# mcu.net
KiCad netlist of a schematic drawn in Altium Designer
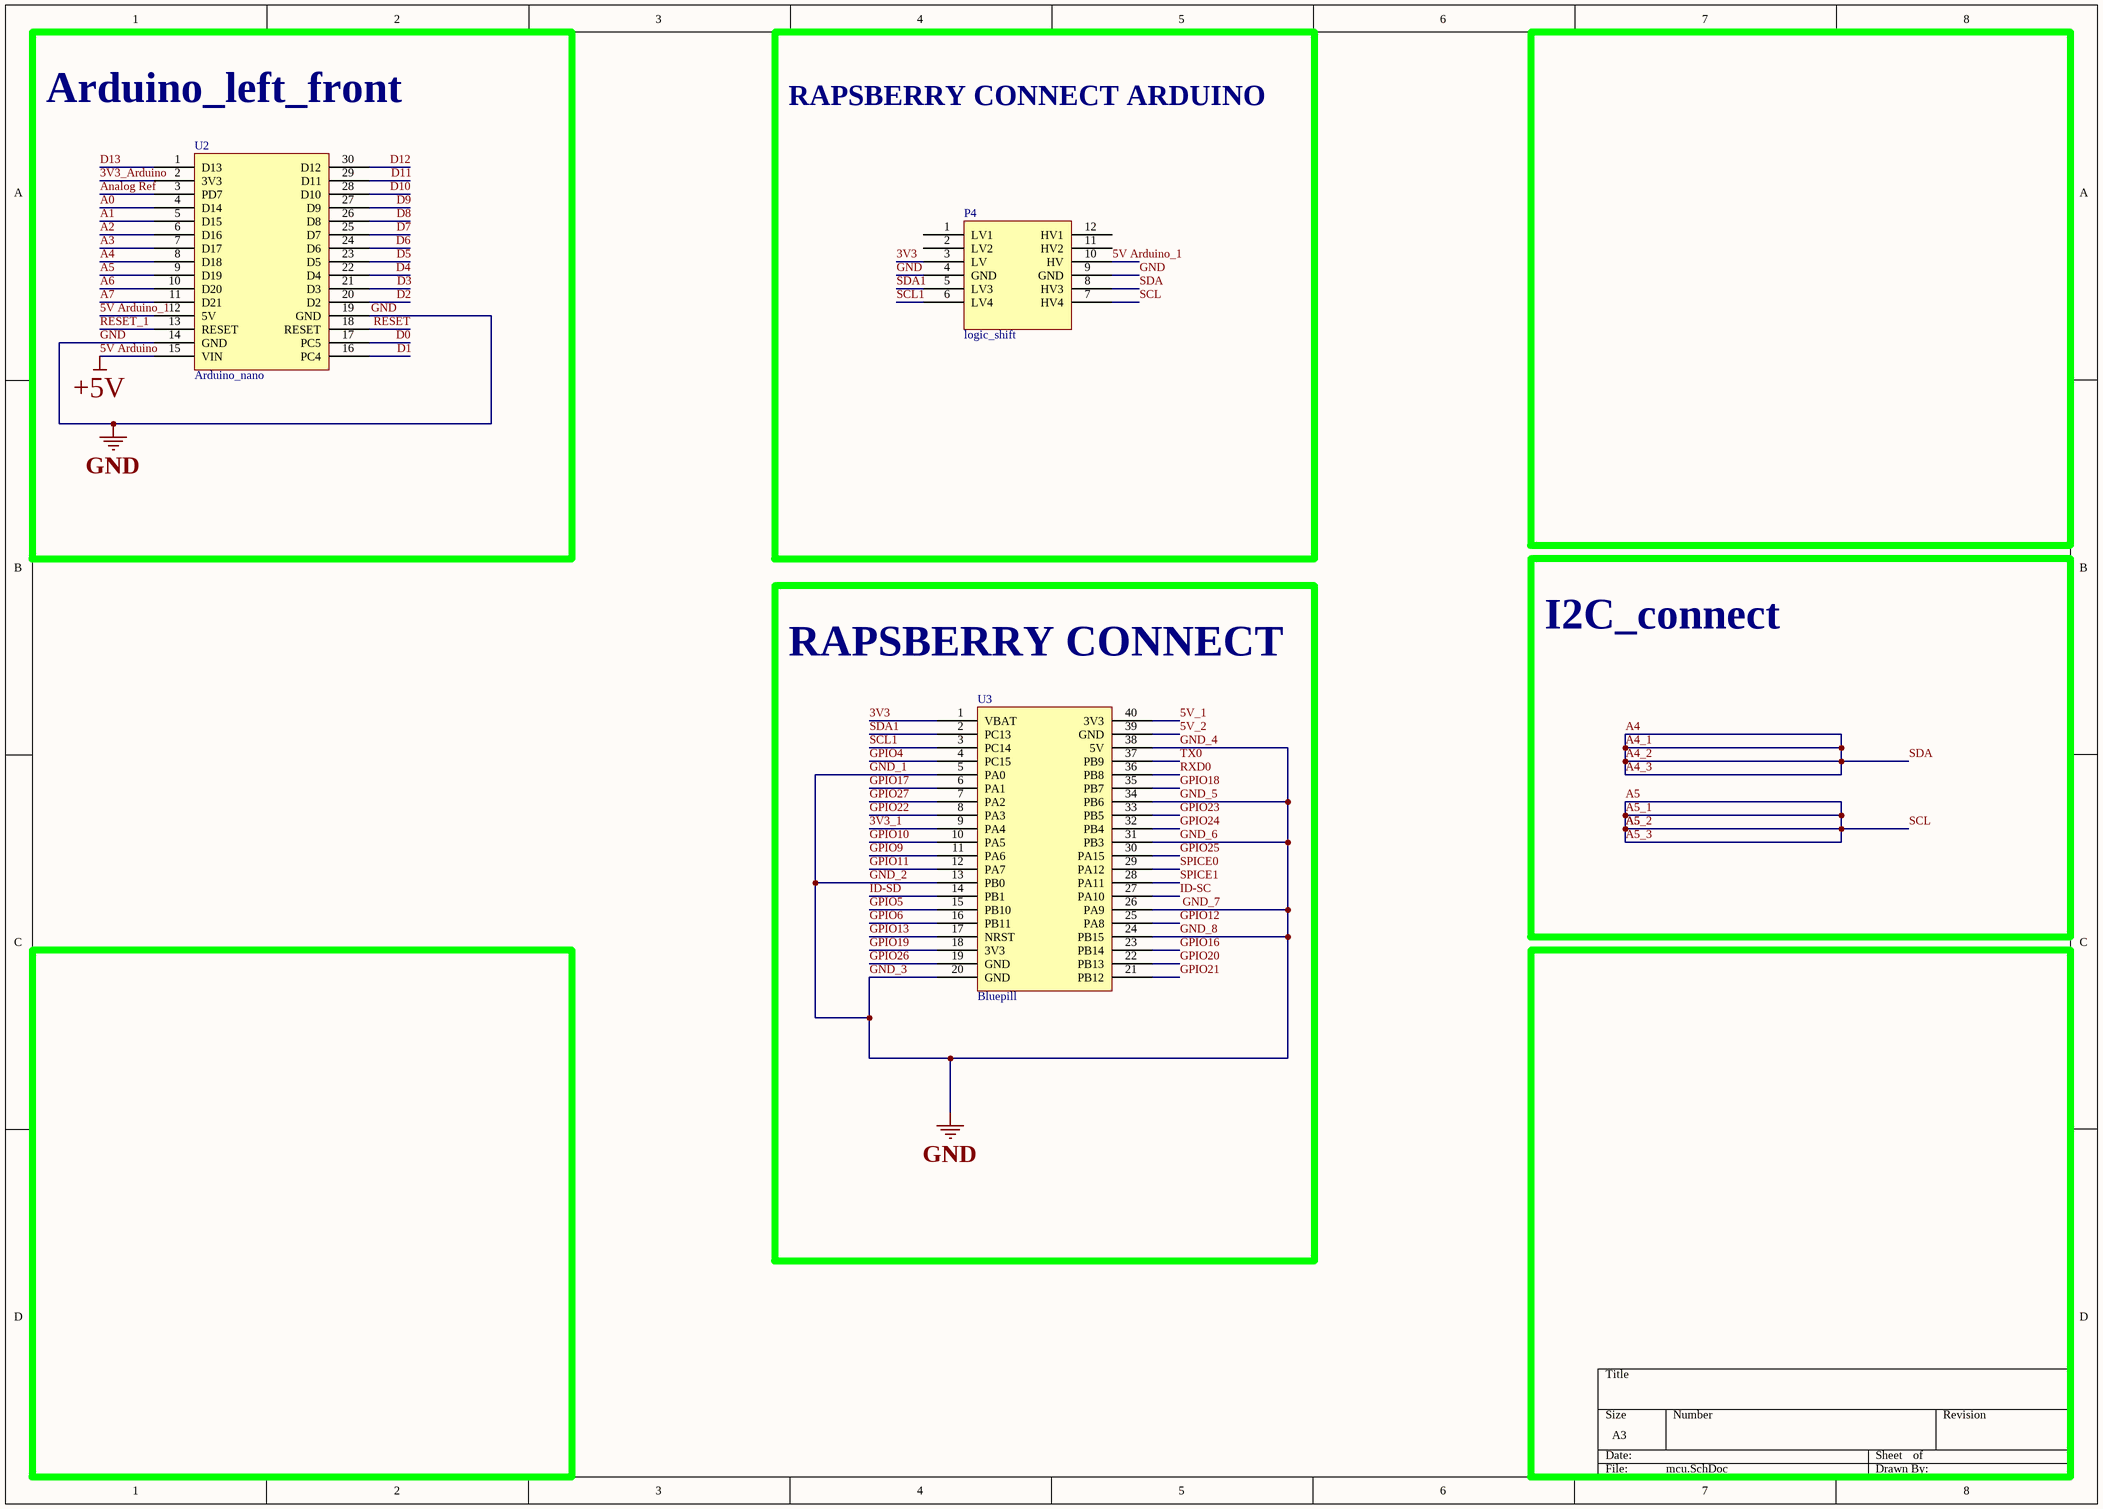
[diagram p0: mcu.SchDoc]

(export (version "E")
  (design (tool "Eeschema 10.0.6"))
  (components
    (comp (ref "P4")
      (value "logic_shift")
      (footprint "logic_convert")
      (libsource (lib "Integrated_Library1") (part "logic_shift"))
    )
    (comp (ref "U2")
      (value "Arduino_nano")
      (footprint "PCBComponent_1")
      (libsource (lib "Integrated_Library1") (part "Arduino_nano"))
    )
    (comp (ref "U3")
      (value "Bluepill")
      (footprint "STM32F103C8T6-Bluepill")
      (libsource (lib "Integrated_Library1") (part "STM32F103C8T6"))
    )
  )
  (nets
    (net (code "1") (name "+5V") (class "Default")
      (node (ref "U2") (pin "15") (pinfunction "VIN_15") (pintype "passive"))
    )
    (net (code "2") (name "/3V3") (class "Default")
      (node (ref "P4") (pin "3") (pinfunction "LV_3") (pintype "passive"))
      (node (ref "U3") (pin "1") (pinfunction "VBAT_1") (pintype "passive"))
    )
    (net (code "3") (name "/3V3_1") (class "Default")
      (node (ref "U3") (pin "9") (pinfunction "PA4_9") (pintype "passive"))
    )
    (net (code "4") (name "/3V3_Arduino") (class "Default")
      (node (ref "U2") (pin "2") (pinfunction "3V3_2") (pintype "passive"))
    )
    (net (code "5") (name "/5V Arduino_1") (class "Default")
      (node (ref "P4") (pin "10") (pinfunction "HV_10") (pintype "passive"))
      (node (ref "U2") (pin "12") (pinfunction "5V_12") (pintype "passive"))
    )
    (net (code "6") (name "/5V_1") (class "Default")
      (node (ref "U3") (pin "40") (pinfunction "3V3_40") (pintype "passive"))
    )
    (net (code "7") (name "/5V_2") (class "Default")
      (node (ref "U3") (pin "39") (pinfunction "GND_39") (pintype "passive"))
    )
    (net (code "8") (name "/A0") (class "Default")
      (node (ref "U2") (pin "4") (pinfunction "D14_4") (pintype "passive"))
    )
    (net (code "9") (name "/A1") (class "Default")
      (node (ref "U2") (pin "5") (pinfunction "D15_5") (pintype "passive"))
    )
    (net (code "10") (name "/A2") (class "Default")
      (node (ref "U2") (pin "6") (pinfunction "D16_6") (pintype "passive"))
    )
    (net (code "11") (name "/A3") (class "Default")
      (node (ref "U2") (pin "7") (pinfunction "D17_7") (pintype "passive"))
    )
    (net (code "12") (name "/A4") (class "Default")
      (node (ref "P4") (pin "8") (pinfunction "HV3_8") (pintype "passive"))
      (node (ref "U2") (pin "8") (pinfunction "D18_8") (pintype "passive"))
    )
    (net (code "13") (name "/A5") (class "Default")
      (node (ref "P4") (pin "7") (pinfunction "HV4_7") (pintype "passive"))
      (node (ref "U2") (pin "9") (pinfunction "D19_9") (pintype "passive"))
    )
    (net (code "14") (name "/A6") (class "Default")
      (node (ref "U2") (pin "10") (pinfunction "D20_10") (pintype "passive"))
    )
    (net (code "15") (name "/A7") (class "Default")
      (node (ref "U2") (pin "11") (pinfunction "D21_11") (pintype "passive"))
    )
    (net (code "16") (name "/Analog Ref") (class "Default")
      (node (ref "U2") (pin "3") (pinfunction "PD7_3") (pintype "passive"))
    )
    (net (code "17") (name "/D0") (class "Default")
      (node (ref "U2") (pin "17") (pinfunction "PC5_17") (pintype "passive"))
    )
    (net (code "18") (name "/D1") (class "Default")
      (node (ref "U2") (pin "16") (pinfunction "PC4_16") (pintype "passive"))
    )
    (net (code "19") (name "/D2") (class "Default")
      (node (ref "U2") (pin "20") (pinfunction "D2_20") (pintype "passive"))
    )
    (net (code "20") (name "/D3") (class "Default")
      (node (ref "U2") (pin "21") (pinfunction "D3_21") (pintype "passive"))
    )
    (net (code "21") (name "/D4") (class "Default")
      (node (ref "U2") (pin "22") (pinfunction "D4_22") (pintype "passive"))
    )
    (net (code "22") (name "/D5") (class "Default")
      (node (ref "U2") (pin "23") (pinfunction "D5_23") (pintype "passive"))
    )
    (net (code "23") (name "/D6") (class "Default")
      (node (ref "U2") (pin "24") (pinfunction "D6_24") (pintype "passive"))
    )
    (net (code "24") (name "/D7") (class "Default")
      (node (ref "U2") (pin "25") (pinfunction "D7_25") (pintype "passive"))
    )
    (net (code "25") (name "/D8") (class "Default")
      (node (ref "U2") (pin "26") (pinfunction "D8_26") (pintype "passive"))
    )
    (net (code "26") (name "/D9") (class "Default")
      (node (ref "U2") (pin "27") (pinfunction "D9_27") (pintype "passive"))
    )
    (net (code "27") (name "/D10") (class "Default")
      (node (ref "U2") (pin "28") (pinfunction "D10_28") (pintype "passive"))
    )
    (net (code "28") (name "/D11") (class "Default")
      (node (ref "U2") (pin "29") (pinfunction "D11_29") (pintype "passive"))
    )
    (net (code "29") (name "/D12") (class "Default")
      (node (ref "U2") (pin "30") (pinfunction "D12_30") (pintype "passive"))
    )
    (net (code "30") (name "/D13") (class "Default")
      (node (ref "U2") (pin "1") (pinfunction "D13_1") (pintype "passive"))
    )
    (net (code "31") (name "/GPIO4") (class "Default")
      (node (ref "U3") (pin "4") (pinfunction "PC15_4") (pintype "passive"))
    )
    (net (code "32") (name "/GPIO5") (class "Default")
      (node (ref "U3") (pin "15") (pinfunction "PB10_15") (pintype "passive"))
    )
    (net (code "33") (name "/GPIO6") (class "Default")
      (node (ref "U3") (pin "16") (pinfunction "PB11_16") (pintype "passive"))
    )
    (net (code "34") (name "/GPIO9") (class "Default")
      (node (ref "U3") (pin "11") (pinfunction "PA6_11") (pintype "passive"))
    )
    (net (code "35") (name "/GPIO10") (class "Default")
      (node (ref "U3") (pin "10") (pinfunction "PA5_10") (pintype "passive"))
    )
    (net (code "36") (name "/GPIO11") (class "Default")
      (node (ref "U3") (pin "12") (pinfunction "PA7_12") (pintype "passive"))
    )
    (net (code "37") (name "/GPIO12") (class "Default")
      (node (ref "U3") (pin "25") (pinfunction "PA8_25") (pintype "passive"))
    )
    (net (code "38") (name "/GPIO13") (class "Default")
      (node (ref "U3") (pin "17") (pinfunction "NRST_17") (pintype "passive"))
    )
    (net (code "39") (name "/GPIO16") (class "Default")
      (node (ref "U3") (pin "23") (pinfunction "PB14_23") (pintype "passive"))
    )
    (net (code "40") (name "/GPIO17") (class "Default")
      (node (ref "U3") (pin "6") (pinfunction "PA1_6") (pintype "passive"))
    )
    (net (code "41") (name "/GPIO18") (class "Default")
      (node (ref "U3") (pin "35") (pinfunction "PB7_35") (pintype "passive"))
    )
    (net (code "42") (name "/GPIO19") (class "Default")
      (node (ref "U3") (pin "18") (pinfunction "3V3_18") (pintype "passive"))
    )
    (net (code "43") (name "/GPIO20") (class "Default")
      (node (ref "U3") (pin "22") (pinfunction "PB13_22") (pintype "passive"))
    )
    (net (code "44") (name "/GPIO21") (class "Default")
      (node (ref "U3") (pin "21") (pinfunction "PB12_21") (pintype "passive"))
    )
    (net (code "45") (name "/GPIO22") (class "Default")
      (node (ref "U3") (pin "8") (pinfunction "PA3_8") (pintype "passive"))
    )
    (net (code "46") (name "/GPIO23") (class "Default")
      (node (ref "U3") (pin "33") (pinfunction "PB5_33") (pintype "passive"))
    )
    (net (code "47") (name "/GPIO24") (class "Default")
      (node (ref "U3") (pin "32") (pinfunction "PB4_32") (pintype "passive"))
    )
    (net (code "48") (name "/GPIO25") (class "Default")
      (node (ref "U3") (pin "30") (pinfunction "PA15_30") (pintype "passive"))
    )
    (net (code "49") (name "/GPIO26") (class "Default")
      (node (ref "U3") (pin "19") (pinfunction "GND_19") (pintype "passive"))
    )
    (net (code "50") (name "/GPIO27") (class "Default")
      (node (ref "U3") (pin "7") (pinfunction "PA2_7") (pintype "passive"))
    )
    (net (code "51") (name "/ID-SC") (class "Default")
      (node (ref "U3") (pin "27") (pinfunction "PA10_27") (pintype "passive"))
    )
    (net (code "52") (name "/ID-SD") (class "Default")
      (node (ref "U3") (pin "14") (pinfunction "PB1_14") (pintype "passive"))
    )
    (net (code "53") (name "/RESET") (class "Default")
      (node (ref "U2") (pin "18") (pinfunction "RESET_18") (pintype "passive"))
    )
    (net (code "54") (name "/RESET_1") (class "Default")
      (node (ref "U2") (pin "13") (pinfunction "RESET_13") (pintype "passive"))
    )
    (net (code "55") (name "/RXD0") (class "Default")
      (node (ref "U3") (pin "36") (pinfunction "PB8_36") (pintype "passive"))
    )
    (net (code "56") (name "/SCL1") (class "Default")
      (node (ref "P4") (pin "6") (pinfunction "LV4_6") (pintype "passive"))
      (node (ref "U3") (pin "3") (pinfunction "PC14_3") (pintype "passive"))
    )
    (net (code "57") (name "/SDA1") (class "Default")
      (node (ref "P4") (pin "5") (pinfunction "LV3_5") (pintype "passive"))
      (node (ref "U3") (pin "2") (pinfunction "PC13_2") (pintype "passive"))
    )
    (net (code "58") (name "/SPICE0") (class "Default")
      (node (ref "U3") (pin "29") (pinfunction "PA12_29") (pintype "passive"))
    )
    (net (code "59") (name "/SPICE1") (class "Default")
      (node (ref "U3") (pin "28") (pinfunction "PA11_28") (pintype "passive"))
    )
    (net (code "60") (name "/TX0") (class "Default")
      (node (ref "U3") (pin "37") (pinfunction "PB9_37") (pintype "passive"))
    )
    (net (code "61") (name "GND") (class "Default")
      (node (ref "P4") (pin "4") (pinfunction "GND_4") (pintype "passive"))
      (node (ref "P4") (pin "9") (pinfunction "GND_9") (pintype "passive"))
      (node (ref "U2") (pin "14") (pinfunction "GND_14") (pintype "passive"))
      (node (ref "U2") (pin "19") (pinfunction "GND_19") (pintype "passive"))
      (node (ref "U3") (pin "13") (pinfunction "PB0_13") (pintype "passive"))
      (node (ref "U3") (pin "20") (pinfunction "GND_20") (pintype "passive"))
      (node (ref "U3") (pin "24") (pinfunction "PB15_24") (pintype "passive"))
      (node (ref "U3") (pin "26") (pinfunction "PA9_26") (pintype "passive"))
      (node (ref "U3") (pin "31") (pinfunction "PB3_31") (pintype "passive"))
      (node (ref "U3") (pin "34") (pinfunction "PB6_34") (pintype "passive"))
      (node (ref "U3") (pin "38") (pinfunction "5V_38") (pintype "passive"))
      (node (ref "U3") (pin "5") (pinfunction "PA0_5") (pintype "passive"))
    )
    (net (code "62") (name "unconnected-(P4-HV1-Pad12)") (class "Default")
      (node (ref "P4") (pin "12") (pinfunction "HV1_12") (pintype "passive"))
    )
    (net (code "63") (name "unconnected-(P4-HV2-Pad11)") (class "Default")
      (node (ref "P4") (pin "11") (pinfunction "HV2_11") (pintype "passive"))
    )
    (net (code "64") (name "unconnected-(P4-LV1-Pad1)") (class "Default")
      (node (ref "P4") (pin "1") (pinfunction "LV1_1") (pintype "passive"))
    )
    (net (code "65") (name "unconnected-(P4-LV2-Pad2)") (class "Default")
      (node (ref "P4") (pin "2") (pinfunction "LV2_2") (pintype "passive"))
    )
  )
)
